# sch_mcu.net
KiCad netlist of a schematic drawn in Altium Designer
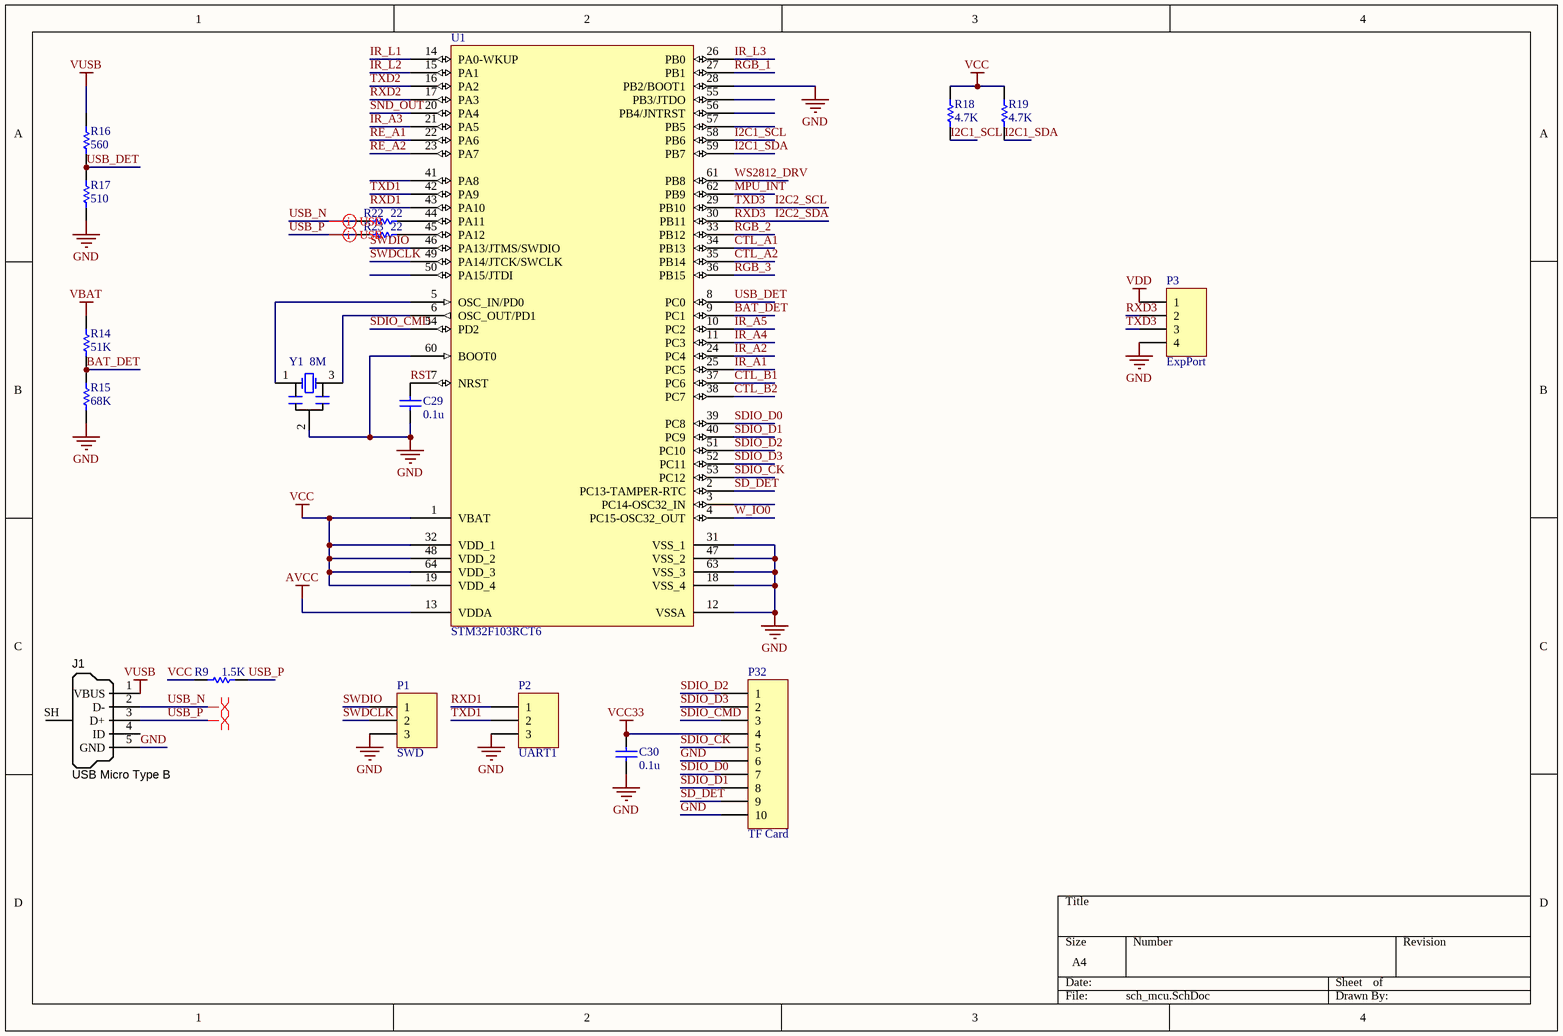
[diagram p0: sch_mcu.SchDoc]

(export (version "E")
  (design (tool "Eeschema 10.0.6"))
  (components
    (comp (ref "C29")
      (value "0.1u")
      (footprint "C-1608[0603]")
      (description "Capacitor (Semiconductor SIM Model)")
      (fields (field (name "Comment") "Cap Semi") (field (name "PUBLISHER") "Altium Limited"))
      (libsource (lib "Miscellaneous Devices") (part "Cap Semi"))
    )
    (comp (ref "C30")
      (value "0.1u")
      (footprint "C-1608[0603]")
      (description "Capacitor (Semiconductor SIM Model)")
      (fields (field (name "Comment") "Cap Semi") (field (name "PUBLISHER") "Altium Limited"))
      (libsource (lib "Miscellaneous Devices") (part "Cap Semi"))
    )
    (comp (ref "J1")
      (value "USB Micro Type B")
      (footprint "MICRO USB 3D")
      (description "Connector SMD USB Micro Type B middle mount")
      (libsource (lib "Schlib1") (part "USB_Micro_TypeB"))
    )
    (comp (ref "P1")
      (value "SWD")
      (footprint "HDR1X3")
      (description "Header, 3-Pin")
      (fields (field (name "PUBLISHER") "Altium Limited"))
      (libsource (lib "Miscellaneous Connectors") (part "Header 3"))
    )
    (comp (ref "P2")
      (value "UART1")
      (footprint "HDR1X3")
      (description "Header, 3-Pin")
      (fields (field (name "PUBLISHER") "Altium Limited"))
      (libsource (lib "Miscellaneous Connectors") (part "Header 3"))
    )
    (comp (ref "P3")
      (value "ExpPort")
      (footprint "HDR1X4")
      (description "Header, 4-Pin")
      (fields (field (name "PUBLISHER") "Altium Limited"))
      (libsource (lib "Miscellaneous Connectors") (part "Header 4"))
    )
    (comp (ref "P32")
      (value "TF Card")
      (footprint "MicroSD auto")
      (description "Header, 10-Pin")
      (fields (field (name "PUBLISHER") "Altium Limited"))
      (libsource (lib "Miscellaneous Connectors") (part "Header 10"))
    )
    (comp (ref "R9")
      (value "1.5K")
      (footprint "R-1608[0603]")
      (description "Semiconductor Resistor")
      (fields (field (name "Comment") "Res Semi") (field (name "PUBLISHER") "Altium Limited"))
      (libsource (lib "Miscellaneous Devices") (part "Res Semi"))
    )
    (comp (ref "R14")
      (value "51K")
      (footprint "R-1608[0603]")
      (description "Semiconductor Resistor")
      (fields (field (name "Comment") "Res Semi") (field (name "PUBLISHER") "Altium Limited"))
      (libsource (lib "Miscellaneous Devices") (part "Res Semi"))
    )
    (comp (ref "R15")
      (value "68K")
      (footprint "R-1608[0603]")
      (description "Semiconductor Resistor")
      (fields (field (name "Comment") "Res Semi") (field (name "PUBLISHER") "Altium Limited"))
      (libsource (lib "Miscellaneous Devices") (part "Res Semi"))
    )
    (comp (ref "R16")
      (value "560")
      (footprint "R-1608[0603]")
      (description "Semiconductor Resistor")
      (fields (field (name "Comment") "Res Semi") (field (name "PUBLISHER") "Altium Limited"))
      (libsource (lib "Miscellaneous Devices") (part "Res Semi"))
    )
    (comp (ref "R17")
      (value "510")
      (footprint "R-1608[0603]")
      (description "Semiconductor Resistor")
      (fields (field (name "Comment") "Res Semi") (field (name "PUBLISHER") "Altium Limited"))
      (libsource (lib "Miscellaneous Devices") (part "Res Semi"))
    )
    (comp (ref "R18")
      (value "4.7K")
      (footprint "R-1608[0603]")
      (description "Semiconductor Resistor")
      (fields (field (name "Comment") "Res Semi") (field (name "PUBLISHER") "Altium Limited"))
      (libsource (lib "Miscellaneous Devices") (part "Res Semi"))
    )
    (comp (ref "R19")
      (value "4.7K")
      (footprint "R-1608[0603]")
      (description "Semiconductor Resistor")
      (fields (field (name "Comment") "Res Semi") (field (name "PUBLISHER") "Altium Limited"))
      (libsource (lib "Miscellaneous Devices") (part "Res Semi"))
    )
    (comp (ref "R22")
      (value "22")
      (footprint "R-1608[0603]")
      (description "Semiconductor Resistor")
      (fields (field (name "Comment") "Res Semi") (field (name "PUBLISHER") "Altium Limited"))
      (libsource (lib "Miscellaneous Devices") (part "Res Semi"))
    )
    (comp (ref "R23")
      (value "22")
      (footprint "R-1608[0603]")
      (description "Semiconductor Resistor")
      (fields (field (name "Comment") "Res Semi") (field (name "PUBLISHER") "Altium Limited"))
      (libsource (lib "Miscellaneous Devices") (part "Res Semi"))
    )
    (comp (ref "U1")
      (value "STM32F103RCT6")
      (footprint "TQFP64_N-3D")
      (description "STM32 ARM-based 32-bit MCU High-density")
      (fields (field (name "PUBLISHER") "Altium Limited"))
      (libsource (lib "ST Microcontroller 32-Bit STM32") (part "STM32F103RBT6"))
    )
    (comp (ref "Y1")
      (value "8M")
      (footprint "Crystal_C")
      (description "Crystal Oscillator")
      (fields (field (name "PUBLISHER") "Altium Limited"))
      (libsource (lib "Schlib1") (part "XTAL_C"))
    )
  )
  (nets
    (net (code "1") (name "/BAT_DET") (class "Default")
      (node (ref "R14") (pin "1") (pinfunction "1_1") (pintype "passive"))
      (node (ref "R15") (pin "1") (pinfunction "1_1") (pintype "passive"))
      (node (ref "U1") (pin "9") (pinfunction "PC1_9") (pintype "bidirectional"))
    )
    (net (code "2") (name "/CTL_A1") (class "Default")
      (node (ref "U1") (pin "34") (pinfunction "PB13_34") (pintype "bidirectional"))
    )
    (net (code "3") (name "/CTL_A2") (class "Default")
      (node (ref "U1") (pin "35") (pinfunction "PB14_35") (pintype "bidirectional"))
    )
    (net (code "4") (name "/CTL_B1") (class "Default")
      (node (ref "U1") (pin "37") (pinfunction "PC6_37") (pintype "bidirectional"))
    )
    (net (code "5") (name "/CTL_B2") (class "Default")
      (node (ref "U1") (pin "38") (pinfunction "PC7_38") (pintype "bidirectional"))
    )
    (net (code "6") (name "/I2C1_SCL") (class "Default")
      (node (ref "R18") (pin "1") (pinfunction "1_1") (pintype "passive"))
      (node (ref "U1") (pin "58") (pinfunction "PB6_58") (pintype "bidirectional"))
    )
    (net (code "7") (name "/I2C1_SDA") (class "Default")
      (node (ref "R19") (pin "1") (pinfunction "1_1") (pintype "passive"))
      (node (ref "U1") (pin "59") (pinfunction "PB7_59") (pintype "bidirectional"))
    )
    (net (code "8") (name "/I2C2_SCL") (class "Default")
      (node (ref "P3") (pin "3") (pinfunction "3_3") (pintype "passive"))
      (node (ref "U1") (pin "29") (pinfunction "PB10_29") (pintype "bidirectional"))
    )
    (net (code "9") (name "/I2C2_SDA") (class "Default")
      (node (ref "P3") (pin "2") (pinfunction "2_2") (pintype "passive"))
      (node (ref "U1") (pin "30") (pinfunction "PB11_30") (pintype "bidirectional"))
    )
    (net (code "10") (name "/IR_A1") (class "Default")
      (node (ref "U1") (pin "25") (pinfunction "PC5_25") (pintype "bidirectional"))
    )
    (net (code "11") (name "/IR_A2") (class "Default")
      (node (ref "U1") (pin "24") (pinfunction "PC4_24") (pintype "bidirectional"))
    )
    (net (code "12") (name "/IR_A3") (class "Default")
      (node (ref "U1") (pin "21") (pinfunction "PA5_21") (pintype "bidirectional"))
    )
    (net (code "13") (name "/IR_A4") (class "Default")
      (node (ref "U1") (pin "11") (pinfunction "PC3_11") (pintype "bidirectional"))
    )
    (net (code "14") (name "/IR_A5") (class "Default")
      (node (ref "U1") (pin "10") (pinfunction "PC2_10") (pintype "bidirectional"))
    )
    (net (code "15") (name "/IR_L1") (class "Default")
      (node (ref "U1") (pin "14") (pinfunction "PA0-WKUP_14") (pintype "bidirectional"))
    )
    (net (code "16") (name "/IR_L2") (class "Default")
      (node (ref "U1") (pin "15") (pinfunction "PA1_15") (pintype "bidirectional"))
    )
    (net (code "17") (name "/IR_L3") (class "Default")
      (node (ref "U1") (pin "26") (pinfunction "PB0_26") (pintype "bidirectional"))
    )
    (net (code "18") (name "/MPU_INT") (class "Default")
      (node (ref "U1") (pin "62") (pinfunction "PB9_62") (pintype "bidirectional"))
    )
    (net (code "19") (name "/RE_A1") (class "Default")
      (node (ref "U1") (pin "22") (pinfunction "PA6_22") (pintype "bidirectional"))
    )
    (net (code "20") (name "/RE_A2") (class "Default")
      (node (ref "U1") (pin "23") (pinfunction "PA7_23") (pintype "bidirectional"))
    )
    (net (code "21") (name "/RGB_1") (class "Default")
      (node (ref "U1") (pin "27") (pinfunction "PB1_27") (pintype "bidirectional"))
    )
    (net (code "22") (name "/RGB_2") (class "Default")
      (node (ref "U1") (pin "33") (pinfunction "PB12_33") (pintype "bidirectional"))
    )
    (net (code "23") (name "/RGB_3") (class "Default")
      (node (ref "U1") (pin "36") (pinfunction "PB15_36") (pintype "bidirectional"))
    )
    (net (code "24") (name "/RST") (class "Default")
      (node (ref "C29") (pin "2") (pinfunction "2_2") (pintype "passive"))
      (node (ref "U1") (pin "7") (pinfunction "NRST_7") (pintype "bidirectional"))
    )
    (net (code "25") (name "/RXD1") (class "Default")
      (node (ref "P2") (pin "1") (pinfunction "1_1") (pintype "passive"))
      (node (ref "U1") (pin "43") (pinfunction "PA10_43") (pintype "bidirectional"))
    )
    (net (code "26") (name "/RXD2") (class "Default")
      (node (ref "U1") (pin "17") (pinfunction "PA3_17") (pintype "bidirectional"))
    )
    (net (code "27") (name "/SDIO_CK") (class "Default")
      (node (ref "P32") (pin "5") (pinfunction "5_5") (pintype "passive"))
      (node (ref "U1") (pin "53") (pinfunction "PC12_53") (pintype "bidirectional"))
    )
    (net (code "28") (name "/SDIO_CMD") (class "Default")
      (node (ref "P32") (pin "3") (pinfunction "3_3") (pintype "passive"))
      (node (ref "U1") (pin "54") (pinfunction "PD2_54") (pintype "bidirectional"))
    )
    (net (code "29") (name "/SDIO_D0") (class "Default")
      (node (ref "P32") (pin "7") (pinfunction "7_7") (pintype "passive"))
      (node (ref "U1") (pin "39") (pinfunction "PC8_39") (pintype "bidirectional"))
    )
    (net (code "30") (name "/SDIO_D1") (class "Default")
      (node (ref "P32") (pin "8") (pinfunction "8_8") (pintype "passive"))
      (node (ref "U1") (pin "40") (pinfunction "PC9_40") (pintype "bidirectional"))
    )
    (net (code "31") (name "/SDIO_D2") (class "Default")
      (node (ref "P32") (pin "1") (pinfunction "1_1") (pintype "passive"))
      (node (ref "U1") (pin "51") (pinfunction "PC10_51") (pintype "bidirectional"))
    )
    (net (code "32") (name "/SDIO_D3") (class "Default")
      (node (ref "P32") (pin "2") (pinfunction "2_2") (pintype "passive"))
      (node (ref "U1") (pin "52") (pinfunction "PC11_52") (pintype "bidirectional"))
    )
    (net (code "33") (name "/SD_DET") (class "Default")
      (node (ref "P32") (pin "9") (pinfunction "9_9") (pintype "passive"))
      (node (ref "U1") (pin "2") (pinfunction "PC13-TAMPER-RTC_2") (pintype "bidirectional"))
    )
    (net (code "34") (name "/SND_OUT") (class "Default")
      (node (ref "U1") (pin "20") (pinfunction "PA4_20") (pintype "bidirectional"))
    )
    (net (code "35") (name "/SWDCLK") (class "Default")
      (node (ref "P1") (pin "2") (pinfunction "2_2") (pintype "passive"))
      (node (ref "U1") (pin "49") (pinfunction "PA14/JTCK/SWCLK_49") (pintype "bidirectional"))
    )
    (net (code "36") (name "/SWDIO") (class "Default")
      (node (ref "P1") (pin "1") (pinfunction "1_1") (pintype "passive"))
      (node (ref "U1") (pin "46") (pinfunction "PA13/JTMS/SWDIO_46") (pintype "bidirectional"))
    )
    (net (code "37") (name "/TXD1") (class "Default")
      (node (ref "P2") (pin "2") (pinfunction "2_2") (pintype "passive"))
      (node (ref "U1") (pin "42") (pinfunction "PA9_42") (pintype "bidirectional"))
    )
    (net (code "38") (name "/TXD2") (class "Default")
      (node (ref "U1") (pin "16") (pinfunction "PA2_16") (pintype "bidirectional"))
    )
    (net (code "39") (name "/USB_DET") (class "Default")
      (node (ref "R16") (pin "1") (pinfunction "1_1") (pintype "passive"))
      (node (ref "R17") (pin "2") (pinfunction "2_2") (pintype "passive"))
      (node (ref "U1") (pin "8") (pinfunction "PC0_8") (pintype "bidirectional"))
    )
    (net (code "40") (name "/USB_N") (class "Default")
      (node (ref "J1") (pin "2") (pinfunction "D-_2") (pintype "passive"))
      (node (ref "R22") (pin "1") (pinfunction "1_1") (pintype "passive"))
    )
    (net (code "41") (name "/USB_P") (class "Default")
      (node (ref "J1") (pin "3") (pinfunction "D+_3") (pintype "passive"))
      (node (ref "R23") (pin "1") (pinfunction "1_1") (pintype "passive"))
      (node (ref "R9") (pin "1") (pinfunction "1_1") (pintype "passive"))
    )
    (net (code "42") (name "/WS2812_DRV") (class "Default")
      (node (ref "U1") (pin "61") (pinfunction "PB8_61") (pintype "bidirectional"))
    )
    (net (code "43") (name "/W_IO0") (class "Default")
      (node (ref "U1") (pin "4") (pinfunction "PC15-OSC32_OUT_4") (pintype "bidirectional"))
    )
    (net (code "44") (name "AVCC") (class "Default")
      (node (ref "U1") (pin "13") (pinfunction "VDDA_13") (pintype "power_in"))
    )
    (net (code "45") (name "GND") (class "Default")
      (node (ref "C29") (pin "1") (pinfunction "1_1") (pintype "passive"))
      (node (ref "C30") (pin "1") (pinfunction "1_1") (pintype "passive"))
      (node (ref "J1") (pin "5") (pinfunction "GND_5") (pintype "passive"))
      (node (ref "P1") (pin "3") (pinfunction "3_3") (pintype "passive"))
      (node (ref "P2") (pin "3") (pinfunction "3_3") (pintype "passive"))
      (node (ref "P3") (pin "4") (pinfunction "4_4") (pintype "passive"))
      (node (ref "P32") (pin "10") (pinfunction "10_10") (pintype "passive"))
      (node (ref "P32") (pin "6") (pinfunction "6_6") (pintype "passive"))
      (node (ref "R15") (pin "2") (pinfunction "2_2") (pintype "passive"))
      (node (ref "R17") (pin "1") (pinfunction "1_1") (pintype "passive"))
      (node (ref "U1") (pin "12") (pinfunction "VSSA_12") (pintype "power_in"))
      (node (ref "U1") (pin "18") (pinfunction "VSS_4_18") (pintype "power_in"))
      (node (ref "U1") (pin "28") (pinfunction "PB2/BOOT1_28") (pintype "bidirectional"))
      (node (ref "U1") (pin "31") (pinfunction "VSS_1_31") (pintype "power_in"))
      (node (ref "U1") (pin "47") (pinfunction "VSS_2_47") (pintype "power_in"))
      (node (ref "U1") (pin "60") (pinfunction "BOOT0_60") (pintype "input"))
      (node (ref "U1") (pin "63") (pinfunction "VSS_3_63") (pintype "power_in"))
      (node (ref "Y1") (pin "2") (pinfunction "GND_2") (pintype "passive"))
    )
    (net (code "46") (name "Net-(U1-OSC_IN{slash}PD0)") (class "Default")
      (node (ref "U1") (pin "5") (pinfunction "OSC_IN/PD0_5") (pintype "input"))
      (node (ref "Y1") (pin "1") (pinfunction "OSC1_1") (pintype "passive"))
    )
    (net (code "47") (name "Net-(U1-OSC_OUT{slash}PD1)") (class "Default")
      (node (ref "U1") (pin "6") (pinfunction "OSC_OUT/PD1_6") (pintype "output"))
      (node (ref "Y1") (pin "3") (pinfunction "OSC2_3") (pintype "passive"))
    )
    (net (code "48") (name "Net-(U1-PA11)") (class "Default")
      (node (ref "R22") (pin "2") (pinfunction "2_2") (pintype "passive"))
      (node (ref "U1") (pin "44") (pinfunction "PA11_44") (pintype "bidirectional"))
    )
    (net (code "49") (name "Net-(U1-PA12)") (class "Default")
      (node (ref "R23") (pin "2") (pinfunction "2_2") (pintype "passive"))
      (node (ref "U1") (pin "45") (pinfunction "PA12_45") (pintype "bidirectional"))
    )
    (net (code "50") (name "VBAT") (class "Default")
      (node (ref "R14") (pin "2") (pinfunction "2_2") (pintype "passive"))
    )
    (net (code "51") (name "VCC") (class "Default")
      (node (ref "R18") (pin "2") (pinfunction "2_2") (pintype "passive"))
      (node (ref "R19") (pin "2") (pinfunction "2_2") (pintype "passive"))
      (node (ref "R9") (pin "2") (pinfunction "2_2") (pintype "passive"))
      (node (ref "U1") (pin "1") (pinfunction "VBAT_1") (pintype "power_in"))
      (node (ref "U1") (pin "19") (pinfunction "VDD_4_19") (pintype "power_in"))
      (node (ref "U1") (pin "32") (pinfunction "VDD_1_32") (pintype "power_in"))
      (node (ref "U1") (pin "48") (pinfunction "VDD_2_48") (pintype "power_in"))
      (node (ref "U1") (pin "64") (pinfunction "VDD_3_64") (pintype "power_in"))
    )
    (net (code "52") (name "VCC33") (class "Default")
      (node (ref "C30") (pin "2") (pinfunction "2_2") (pintype "passive"))
      (node (ref "P32") (pin "4") (pinfunction "4_4") (pintype "passive"))
    )
    (net (code "53") (name "VDD") (class "Default")
      (node (ref "P3") (pin "1") (pinfunction "1_1") (pintype "passive"))
    )
    (net (code "54") (name "VUSB") (class "Default")
      (node (ref "J1") (pin "1") (pinfunction "VBUS_1") (pintype "passive"))
      (node (ref "R16") (pin "2") (pinfunction "2_2") (pintype "passive"))
    )
    (net (code "55") (name "unconnected-(J1-ID-Pad4)") (class "Default")
      (node (ref "J1") (pin "4") (pinfunction "ID_4") (pintype "passive"))
    )
    (net (code "56") (name "unconnected-(J1-Shell-PadSH)") (class "Default")
      (node (ref "J1") (pin "SH") (pinfunction "Shell_SH") (pintype "passive"))
    )
    (net (code "57") (name "unconnected-(U1-PA8-Pad41)") (class "Default")
      (node (ref "U1") (pin "41") (pinfunction "PA8_41") (pintype "bidirectional"))
    )
    (net (code "58") (name "unconnected-(U1-PA15{slash}JTDI-Pad50)") (class "Default")
      (node (ref "U1") (pin "50") (pinfunction "PA15/JTDI_50") (pintype "bidirectional"))
    )
    (net (code "59") (name "unconnected-(U1-PB3{slash}JTDO-Pad55)") (class "Default")
      (node (ref "U1") (pin "55") (pinfunction "PB3/JTDO_55") (pintype "bidirectional"))
    )
    (net (code "60") (name "unconnected-(U1-PB4{slash}JNTRST-Pad56)") (class "Default")
      (node (ref "U1") (pin "56") (pinfunction "PB4/JNTRST_56") (pintype "bidirectional"))
    )
    (net (code "61") (name "unconnected-(U1-PB5-Pad57)") (class "Default")
      (node (ref "U1") (pin "57") (pinfunction "PB5_57") (pintype "bidirectional"))
    )
    (net (code "62") (name "unconnected-(U1-PC14-OSC32_IN-Pad3)") (class "Default")
      (node (ref "U1") (pin "3") (pinfunction "PC14-OSC32_IN_3") (pintype "bidirectional"))
    )
  )
)
